# mini-c3.net
KiCad netlist of a schematic drawn in EasyEDA Pro
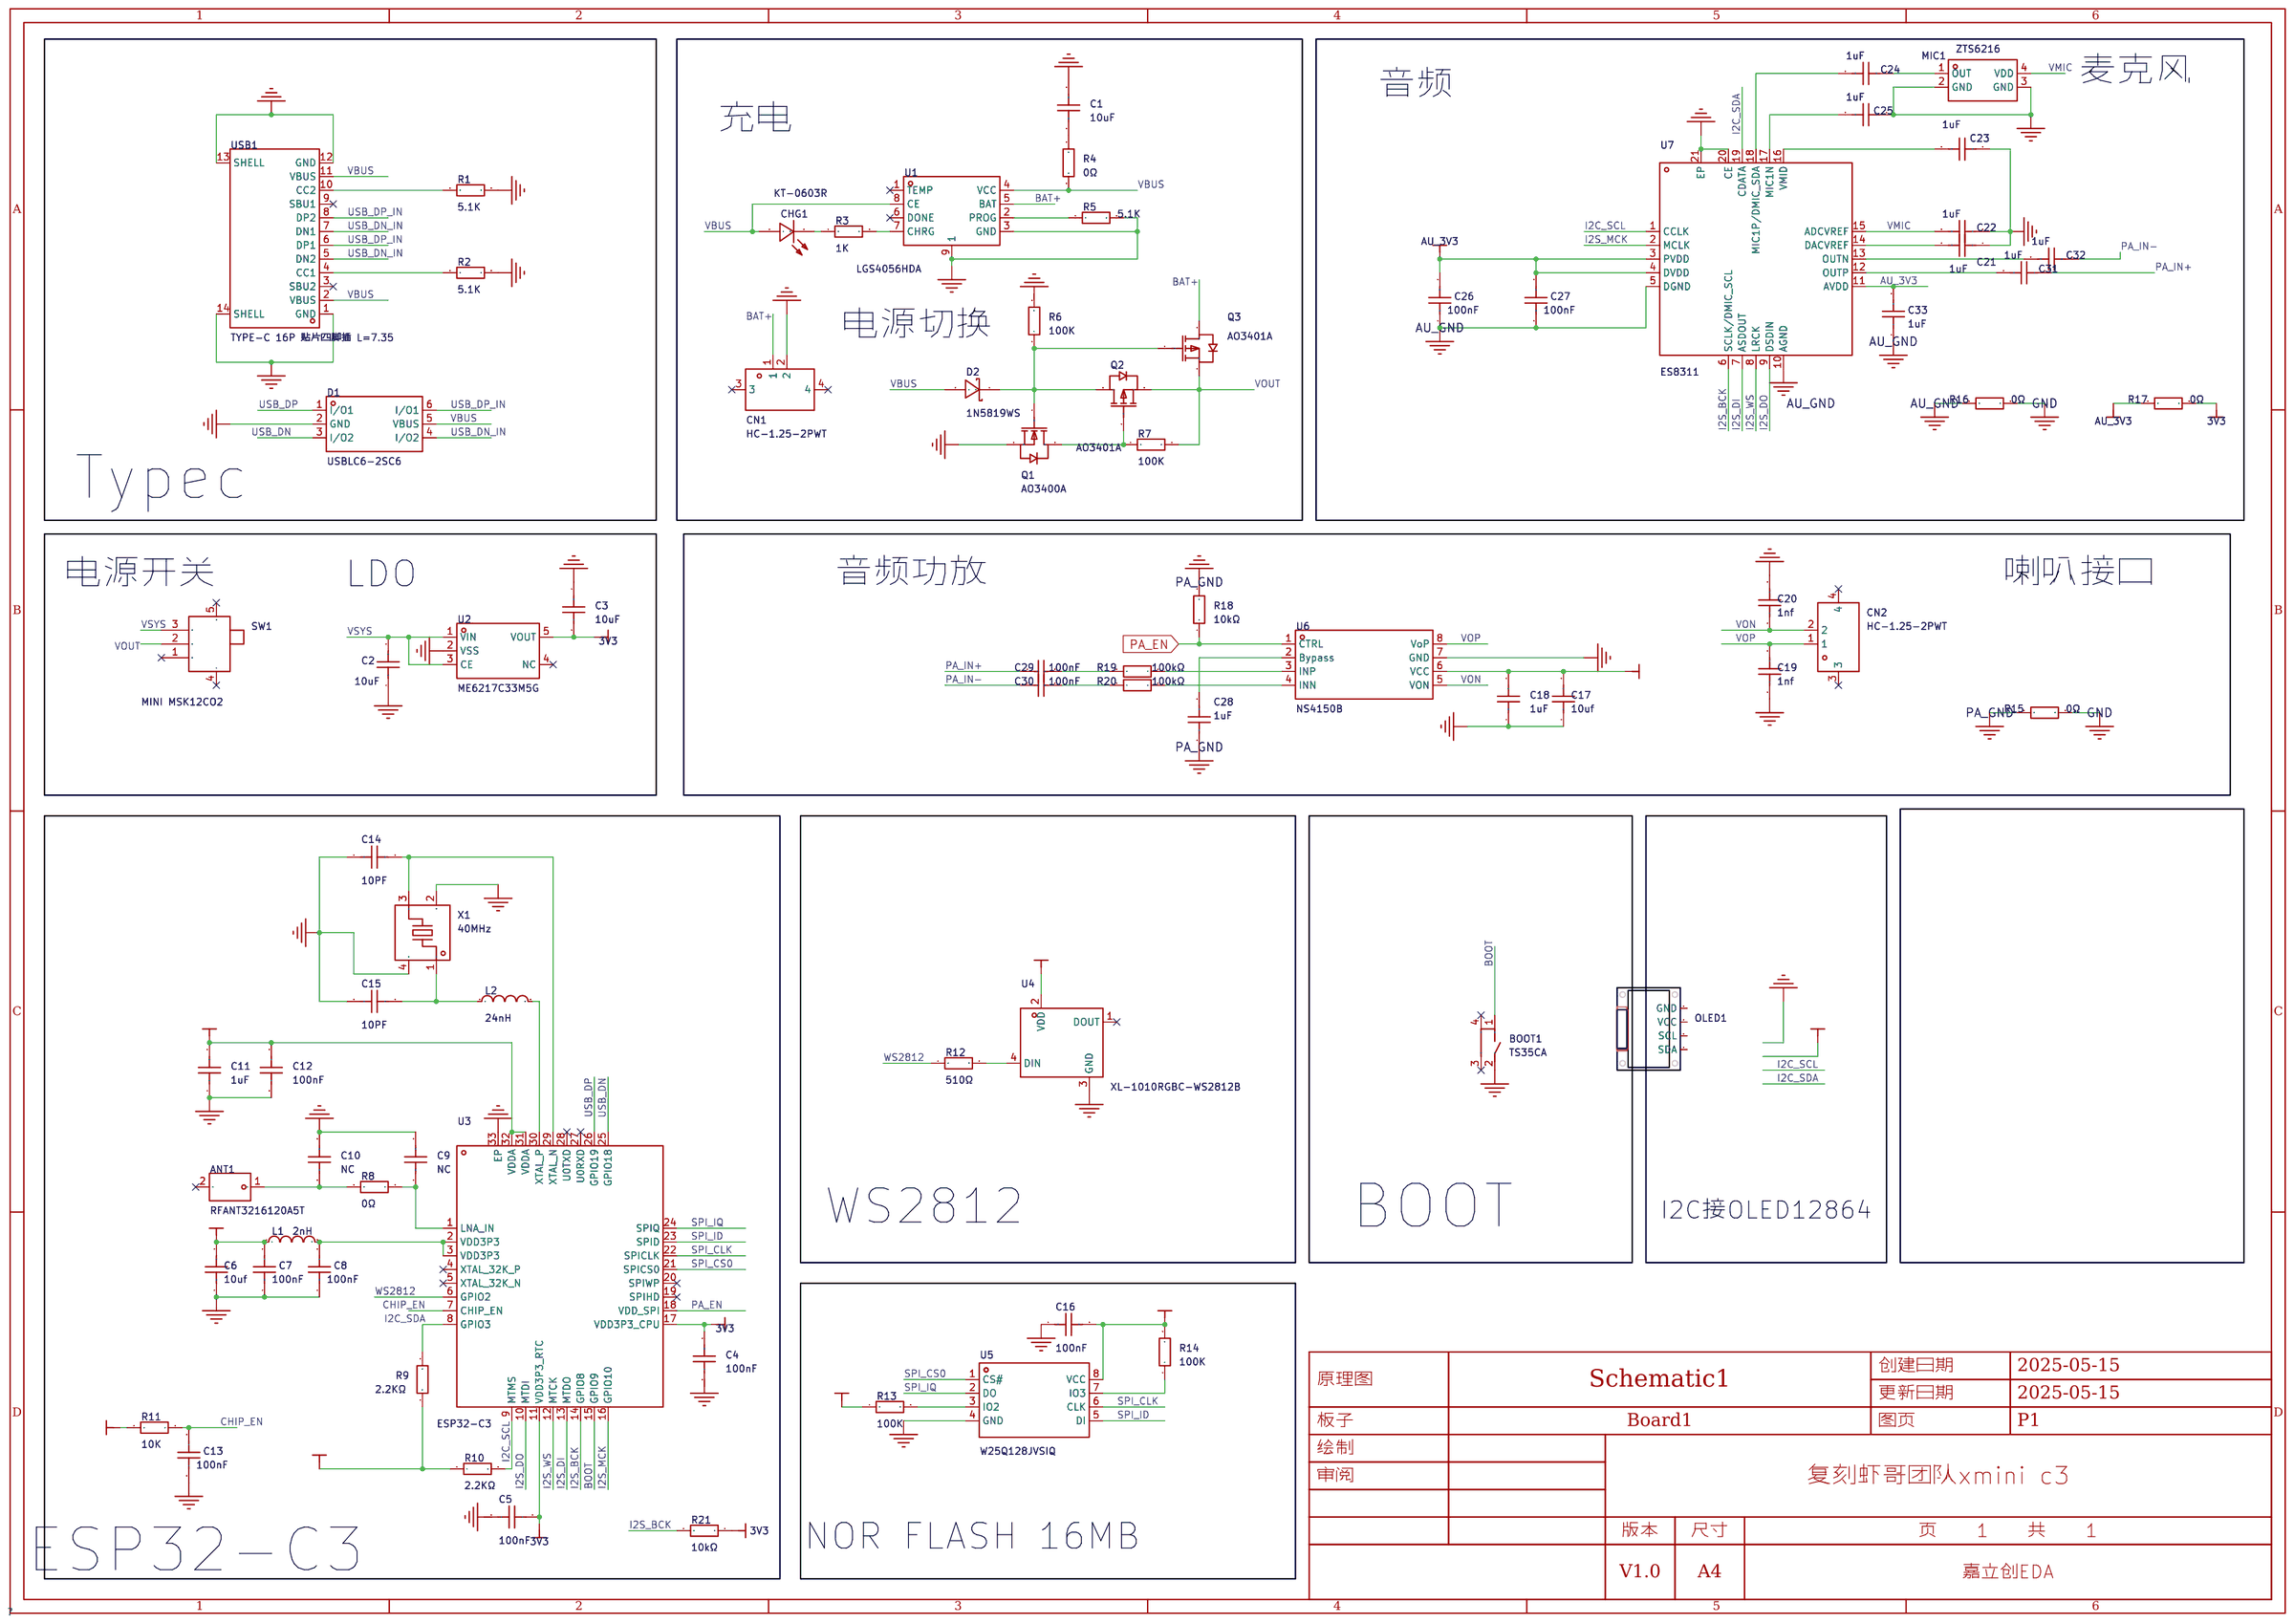
[diagram p0: schematic sheet]

(export (version "E")
  (design (tool "Eeschema 10.0.6"))
  (components
    (comp (ref "ANT1")
      (value "RFANT3216120A5T")
      (footprint "easyedapro:FILTER-SMD_1206-2P-L3.2-W1.6-L")
      (fields (field (name "Manufacturer") "Walsin(华新科)"))
      (libsource (lib "easyedapro") (part "RFANT3216120A5T"))
    )
    (comp (ref "BOOT1")
      (value "TS35CA")
      (footprint "easyedapro:KEY-SMD_TS35CA")
      (fields (field (name "Manufacturer") "SHOU HAN(首韩)"))
      (libsource (lib "easyedapro") (part "TS35CA"))
    )
    (comp (ref "C1")
      (value "10uF")
      (footprint "easyedapro:C0402")
      (libsource (lib "easyedapro") (part "CapAcitance"))
    )
    (comp (ref "C2")
      (value "10uF")
      (footprint "easyedapro:C0402")
      (libsource (lib "easyedapro") (part "CapAcitance"))
    )
    (comp (ref "C3")
      (value "10uF")
      (footprint "easyedapro:C0402")
      (libsource (lib "easyedapro") (part "CapAcitance"))
    )
    (comp (ref "C4")
      (value "100nF")
      (footprint "easyedapro:C0402")
      (libsource (lib "easyedapro") (part "CapAcitance"))
    )
    (comp (ref "C5")
      (value "100nF")
      (footprint "easyedapro:C0402")
      (libsource (lib "easyedapro") (part "CapAcitance"))
    )
    (comp (ref "C6")
      (value "10uf")
      (footprint "easyedapro:C0402")
      (libsource (lib "easyedapro") (part "CapAcitance"))
    )
    (comp (ref "C7")
      (value "100nF")
      (footprint "easyedapro:C0402")
      (libsource (lib "easyedapro") (part "CapAcitance"))
    )
    (comp (ref "C8")
      (value "100nF")
      (footprint "easyedapro:C0402")
      (libsource (lib "easyedapro") (part "CapAcitance"))
    )
    (comp (ref "C9")
      (value "NC")
      (footprint "easyedapro:C0402")
      (libsource (lib "easyedapro") (part "CapAcitance"))
    )
    (comp (ref "C10")
      (value "NC")
      (footprint "easyedapro:C0402")
      (libsource (lib "easyedapro") (part "CapAcitance"))
    )
    (comp (ref "C11")
      (value "1uF")
      (footprint "easyedapro:C0402")
      (libsource (lib "easyedapro") (part "CapAcitance"))
    )
    (comp (ref "C12")
      (value "100nF")
      (footprint "easyedapro:C0402")
      (libsource (lib "easyedapro") (part "CapAcitance"))
    )
    (comp (ref "C13")
      (value "100nF")
      (footprint "easyedapro:C0402")
      (libsource (lib "easyedapro") (part "CapAcitance"))
    )
    (comp (ref "C14")
      (value "10PF")
      (footprint "easyedapro:C0402")
      (libsource (lib "easyedapro") (part "CapAcitance"))
    )
    (comp (ref "C15")
      (value "10PF")
      (footprint "easyedapro:C0402")
      (libsource (lib "easyedapro") (part "CapAcitance"))
    )
    (comp (ref "C16")
      (value "100nF")
      (footprint "easyedapro:C0402")
      (libsource (lib "easyedapro") (part "CapAcitance"))
    )
    (comp (ref "C17")
      (value "10uf")
      (footprint "easyedapro:C0402")
      (libsource (lib "easyedapro") (part "CapAcitance"))
    )
    (comp (ref "C18")
      (value "1uF")
      (footprint "easyedapro:C0402")
      (libsource (lib "easyedapro") (part "CapAcitance"))
    )
    (comp (ref "C19")
      (value "1nf")
      (footprint "easyedapro:C0402")
      (libsource (lib "easyedapro") (part "CapAcitance"))
    )
    (comp (ref "C20")
      (value "1nf")
      (footprint "easyedapro:C0402")
      (libsource (lib "easyedapro") (part "CapAcitance"))
    )
    (comp (ref "C21")
      (value "1uF")
      (footprint "easyedapro:C0402")
      (libsource (lib "easyedapro") (part "CapAcitance"))
    )
    (comp (ref "C22")
      (value "1uF")
      (footprint "easyedapro:C0402")
      (libsource (lib "easyedapro") (part "CapAcitance"))
    )
    (comp (ref "C23")
      (value "1uF")
      (footprint "easyedapro:C0402")
      (libsource (lib "easyedapro") (part "CapAcitance"))
    )
    (comp (ref "C24")
      (value "1uF")
      (footprint "easyedapro:C0402")
      (libsource (lib "easyedapro") (part "CapAcitance"))
    )
    (comp (ref "C25")
      (value "1uF")
      (footprint "easyedapro:C0402")
      (libsource (lib "easyedapro") (part "CapAcitance"))
    )
    (comp (ref "C26")
      (value "100nF")
      (footprint "easyedapro:C0402")
      (libsource (lib "easyedapro") (part "CapAcitance"))
    )
    (comp (ref "C27")
      (value "100nF")
      (footprint "easyedapro:C0402")
      (libsource (lib "easyedapro") (part "CapAcitance"))
    )
    (comp (ref "C28")
      (value "1uF")
      (footprint "easyedapro:C0402")
      (fields
        (field (name "Manufacturer Part") "CL05A105KA5NQNC")
        (field (name "Manufacturer") "SAMSUNG(三星)")
      )
      (libsource (lib "easyedapro") (part "CL05A105KA5NQNC"))
    )
    (comp (ref "C29")
      (value "100nF")
      (footprint "easyedapro:C0402")
      (fields
        (field (name "Manufacturer Part") "CL05B104KO5NNNC")
        (field (name "Manufacturer") "SAMSUNG(三星)")
      )
      (libsource (lib "easyedapro") (part "CL05B104KO5NNNC"))
    )
    (comp (ref "C30")
      (value "100nF")
      (footprint "easyedapro:C0402")
      (fields
        (field (name "Manufacturer Part") "CL05B104KO5NNNC")
        (field (name "Manufacturer") "SAMSUNG(三星)")
      )
      (libsource (lib "easyedapro") (part "CL05B104KO5NNNC"))
    )
    (comp (ref "C31")
      (value "1uF")
      (footprint "easyedapro:C0402")
      (libsource (lib "easyedapro") (part "CapAcitance"))
    )
    (comp (ref "C32")
      (value "1uF")
      (footprint "easyedapro:C0402")
      (libsource (lib "easyedapro") (part "CapAcitance"))
    )
    (comp (ref "C33")
      (value "1uF")
      (footprint "easyedapro:C0402")
      (fields
        (field (name "Manufacturer Part") "CL05A105KA5NQNC")
        (field (name "Manufacturer") "SAMSUNG(三星)")
      )
      (libsource (lib "easyedapro") (part "CL05A105KA5NQNC"))
    )
    (comp (ref "CHG1")
      (value "KT-0603R")
      (footprint "easyedapro:LED0603-RD")
      (fields (field (name "Manufacturer") "KENTO"))
      (libsource (lib "easyedapro") (part "KT-0603R"))
    )
    (comp (ref "CN1")
      (value "HC-1.25-2PWT")
      (footprint "easyedapro:CONN-SMD_2P-P1.25-HC-1.25-2PWT")
      (fields (field (name "Manufacturer") "HCTL(华灿天禄)"))
      (libsource (lib "easyedapro") (part "HC-1.25-2PWT"))
    )
    (comp (ref "CN2")
      (value "HC-1.25-2PWT")
      (footprint "easyedapro:CONN-SMD_2P-P1.25-HC-1.25-2PWT")
      (fields (field (name "Manufacturer") "HCTL(华灿天禄)"))
      (libsource (lib "easyedapro") (part "HC-1.25-2PWT"))
    )
    (comp (ref "D1")
      (value "USBLC6-2SC6")
      (footprint "easyedapro:SOT-23-6_L2.9-W1.6-P0.95-LS2.8-BL")
      (fields (field (name "Manufacturer") "UMW(友台半导体)"))
      (libsource (lib "easyedapro") (part "USBLC6-2SC6_C2687116"))
    )
    (comp (ref "D2")
      (value "1N5819WS")
      (footprint "easyedapro:SOD-323_L1.8-W1.3-LS2.5-RD")
      (fields (field (name "Manufacturer") "Hottech(合科泰)"))
      (libsource (lib "easyedapro") (part "1N5819WS"))
    )
    (comp (ref "L1")
      (value "2nH")
      (footprint "easyedapro:L0402")
      (libsource (lib "easyedapro") (part "SDCL1005C10NJTDFM01"))
    )
    (comp (ref "L2")
      (value "24nH")
      (footprint "easyedapro:L0402")
      (libsource (lib "easyedapro") (part "SDCL1005C10NJTDFM01"))
    )
    (comp (ref "MIC1")
      (value "ZTS6216")
      (footprint "easyedapro:MIC-SMD_4P-L2.8-W1.9-P1.84-TL")
      (description "方向:全指向;信噪比:65dB;灵敏度:-38dB;阻抗:100Ω;")
      (fields (field (name "Manufacturer") "ZILLTEK(钰太)"))
      (libsource (lib "easyedapro") (part "ZTS6216"))
    )
    (comp (ref "OLED1")
      (value "~")
      (footprint "easyedapro:0.96OLED_4P")
      (libsource (lib "easyedapro") (part "0.96OLED模块_4P"))
    )
    (comp (ref "Q1")
      (value "AO3400A")
      (footprint "easyedapro:SOT-23-3_L2.9-W1.3-P1.90-LS2.4-BR")
      (fields (field (name "Manufacturer") "AOS"))
      (libsource (lib "easyedapro") (part "AO3400A"))
    )
    (comp (ref "Q2")
      (value "AO3401A")
      (footprint "easyedapro:SOT-23_L2.9-W1.3-P1.90-LS2.4-BR")
      (fields (field (name "Manufacturer") "AOS"))
      (libsource (lib "easyedapro") (part "AO3401A"))
    )
    (comp (ref "Q3")
      (value "AO3401A")
      (footprint "easyedapro:SOT-23_L2.9-W1.3-P1.90-LS2.4-BR")
      (fields (field (name "Manufacturer") "AOS"))
      (libsource (lib "easyedapro") (part "AO3401A"))
    )
    (comp (ref "R1") (value "5.1K") (footprint "easyedapro:R0402") (libsource (lib "easyedapro") (part "电阻")))
    (comp (ref "R2") (value "5.1K") (footprint "easyedapro:R0402") (libsource (lib "easyedapro") (part "电阻")))
    (comp (ref "R3") (value "1K") (footprint "easyedapro:R0402") (libsource (lib "easyedapro") (part "电阻")))
    (comp (ref "R4") (value "0Ω") (footprint "easyedapro:R0402") (libsource (lib "easyedapro") (part "电阻")))
    (comp (ref "R5") (value "5.1K") (footprint "easyedapro:R0402") (libsource (lib "easyedapro") (part "电阻")))
    (comp (ref "R6") (value "100K") (footprint "easyedapro:R0402") (libsource (lib "easyedapro") (part "电阻")))
    (comp (ref "R7") (value "100K") (footprint "easyedapro:R0402") (libsource (lib "easyedapro") (part "电阻")))
    (comp (ref "R8") (value "0Ω") (footprint "easyedapro:R0402") (libsource (lib "easyedapro") (part "电阻")))
    (comp (ref "R9")
      (value "2.2KΩ")
      (footprint "easyedapro:R0402")
      (libsource (lib "easyedapro") (part "电阻"))
    )
    (comp (ref "R10")
      (value "2.2KΩ")
      (footprint "easyedapro:R0402")
      (libsource (lib "easyedapro") (part "电阻"))
    )
    (comp (ref "R11") (value "10K") (footprint "easyedapro:R0402") (libsource (lib "easyedapro") (part "电阻")))
    (comp (ref "R12")
      (value "510Ω")
      (footprint "easyedapro:R0402")
      (libsource (lib "easyedapro") (part "电阻"))
    )
    (comp (ref "R13")
      (value "100K")
      (footprint "easyedapro:R0402")
      (libsource (lib "easyedapro") (part "电阻"))
    )
    (comp (ref "R14")
      (value "100K")
      (footprint "easyedapro:R0402")
      (libsource (lib "easyedapro") (part "电阻"))
    )
    (comp (ref "R15")
      (value "0Ω")
      (footprint "easyedapro:R0402")
      (fields
        (field (name "Manufacturer Part") "0402WGF0000TCE")
        (field (name "Manufacturer") "UNI-ROYAL(厚声)")
      )
      (libsource (lib "easyedapro") (part "0402WGF0000TCE"))
    )
    (comp (ref "R16")
      (value "0Ω")
      (footprint "easyedapro:R0402")
      (fields
        (field (name "Manufacturer Part") "0402WGF0000TCE")
        (field (name "Manufacturer") "UNI-ROYAL(厚声)")
      )
      (libsource (lib "easyedapro") (part "0402WGF0000TCE"))
    )
    (comp (ref "R17")
      (value "0Ω")
      (footprint "easyedapro:R0402")
      (fields
        (field (name "Manufacturer Part") "0402WGF0000TCE")
        (field (name "Manufacturer") "UNI-ROYAL(厚声)")
      )
      (libsource (lib "easyedapro") (part "0402WGF0000TCE"))
    )
    (comp (ref "R18")
      (value "10kΩ")
      (footprint "easyedapro:R0402")
      (fields
        (field (name "Manufacturer Part") "0402WGF1002TCE")
        (field (name "Manufacturer") "UNI-ROYAL(厚声)")
      )
      (libsource (lib "easyedapro") (part "0402WGF1002TCE"))
    )
    (comp (ref "R19")
      (value "100kΩ")
      (footprint "easyedapro:R0402")
      (fields
        (field (name "Manufacturer Part") "0402WGF1003TCE")
        (field (name "Manufacturer") "UNI-ROYAL(厚声)")
      )
      (libsource (lib "easyedapro") (part "0402WGF1003TCE"))
    )
    (comp (ref "R20")
      (value "100kΩ")
      (footprint "easyedapro:R0402")
      (fields
        (field (name "Manufacturer Part") "0402WGF1003TCE")
        (field (name "Manufacturer") "UNI-ROYAL(厚声)")
      )
      (libsource (lib "easyedapro") (part "0402WGF1003TCE"))
    )
    (comp (ref "R21")
      (value "10kΩ")
      (footprint "easyedapro:R0402")
      (fields
        (field (name "Manufacturer Part") "0402WGF1002TCE")
        (field (name "Manufacturer") "UNI-ROYAL(厚声)")
      )
      (libsource (lib "easyedapro") (part "0402WGF1002TCE"))
    )
    (comp (ref "SW1")
      (value "MINI MSK12CO2")
      (footprint "easyedapro:SW-SMD_MSK12CO2")
      (fields (field (name "Manufacturer") "SHOU HAN(首韩)"))
      (libsource (lib "easyedapro") (part "MINI MSK12CO2"))
    )
    (comp (ref "U1")
      (value "LGS4056HDA")
      (footprint "easyedapro:DFN-8_L2.0-W2.0-P0.50-TL-EP1.6")
      (fields (field (name "Manufacturer") "Legend-Si(棱晶半导体)"))
      (libsource (lib "easyedapro") (part "LGS4056H"))
    )
    (comp (ref "U2")
      (value "ME6217C33M5G")
      (footprint "easyedapro:SOT-23-5_L3.0-W1.7-P0.95-LS2.8-BR")
      (fields (field (name "Manufacturer") "MICRONE(南京微盟)"))
      (libsource (lib "easyedapro") (part "ME6217C33M5G"))
    )
    (comp (ref "U3")
      (value "ESP32-C3")
      (footprint "easyedapro:QFN-32_L5.0-W5.0-P0.50-TL-EP3.7")
      (fields (field (name "Manufacturer") "ESPRESSIF(乐鑫)"))
      (libsource (lib "easyedapro") (part "ESP32-C3"))
    )
    (comp (ref "U4")
      (value "XL-1010RGBC-WS2812B")
      (footprint "easyedapro:LED-SMD_4P-L1.0-W1.0-TL_XL-1010RGBC-WS2812B")
      (fields (field (name "Manufacturer") "XINGLIGHT(成兴光)"))
      (libsource (lib "easyedapro") (part "XL-1010RGBC-WS2812B"))
    )
    (comp (ref "U5")
      (value "W25Q128JVSIQ")
      (footprint "easyedapro:SOIC-8_L5.3-W5.3-P1.27-LS8.0-BL")
      (fields (field (name "Manufacturer") "WINBOND(华邦)"))
      (libsource (lib "easyedapro") (part "W25Q128JVSIQTR"))
    )
    (comp (ref "U6")
      (value "NS4150B")
      (footprint "easyedapro:MSOP-8_L3.0-W3.0-P0.65-LS5.0-BL")
      (fields (field (name "Manufacturer") "Nsiway(纳芯威)"))
      (libsource (lib "easyedapro") (part "NS4150"))
    )
    (comp (ref "U7")
      (value "ES8311")
      (footprint "easyedapro:WQFN-20_L3.0-W3.0-P0.40-BL-EP1.7")
      (fields (field (name "Manufacturer") "Everest-semi(顺芯)"))
      (libsource (lib "easyedapro") (part "ES8311"))
    )
    (comp (ref "USB1")
      (value "TYPE-C 16P 贴片四脚插 L=7.35")
      (footprint "easyedapro:USB-C-SMD_TYPE-C-6PIN-2MD-073")
      (libsource (lib "easyedapro") (part "TYPE-C 16P 贴片四脚插 L=7.35"))
    )
    (comp (ref "X1")
      (value "40MHz")
      (footprint "easyedapro:CRYSTAL-SMD_4P-L2.5-W2.0-BL")
      (fields (field (name "Manufacturer Part") "X252040MMB4SI") (field (name "Manufacturer") "YXC(扬兴晶振)"))
      (libsource (lib "easyedapro") (part "X252040MMB4SI"))
    )
  )
  (nets
    (net (code "1") (name "/BAT+") (class "Default")
      (node (ref "CN1") (pin "1") (pinfunction "1_1") (pintype "unspecified"))
      (node (ref "Q3") (pin "3") (pinfunction "D_3") (pintype "unspecified"))
      (node (ref "U1") (pin "5") (pinfunction "BAT_5") (pintype "unspecified"))
    )
    (net (code "2") (name "/BOOT") (class "Default")
      (node (ref "BOOT1") (pin "1") (pinfunction "1_1") (pintype "unspecified"))
      (node (ref "U3") (pin "15") (pinfunction "GPIO9_15") (pintype "unspecified"))
    )
    (net (code "3") (name "/CHIP_EN") (class "Default")
      (node (ref "C13") (pin "2") (pinfunction "2_2") (pintype "input"))
      (node (ref "R11") (pin "2") (pinfunction "2_2") (pintype "input"))
      (node (ref "U3") (pin "7") (pinfunction "CHIP_EN_7") (pintype "unspecified"))
    )
    (net (code "4") (name "/I2C_SCL") (class "Default")
      (node (ref "R10") (pin "2") (pinfunction "2_2") (pintype "input"))
      (node (ref "U3") (pin "9") (pinfunction "MTMS_9") (pintype "unspecified"))
      (node (ref "U7") (pin "1") (pinfunction "CCLK_1") (pintype "input"))
    )
    (net (code "5") (name "/I2C_SDA") (class "Default")
      (node (ref "R9") (pin "2") (pinfunction "2_2") (pintype "input"))
      (node (ref "U3") (pin "8") (pinfunction "GPIO3_8") (pintype "unspecified"))
      (node (ref "U7") (pin "19") (pinfunction "CDATA_19") (pintype "input"))
    )
    (net (code "6") (name "/I2S_BCK") (class "Default")
      (node (ref "R21") (pin "2") (pinfunction "2_2") (pintype "input"))
      (node (ref "U3") (pin "14") (pinfunction "GPIO8_14") (pintype "unspecified"))
      (node (ref "U7") (pin "6") (pinfunction "SCLK/DMIC_SCL_6") (pintype "input"))
    )
    (net (code "7") (name "/I2S_DI") (class "Default")
      (node (ref "U3") (pin "13") (pinfunction "MTDO_13") (pintype "unspecified"))
      (node (ref "U7") (pin "7") (pinfunction "ASDOUT_7") (pintype "input"))
    )
    (net (code "8") (name "/I2S_DO") (class "Default")
      (node (ref "U3") (pin "10") (pinfunction "MTDI_10") (pintype "unspecified"))
      (node (ref "U7") (pin "9") (pinfunction "DSDIN_9") (pintype "input"))
    )
    (net (code "9") (name "/I2S_MCK") (class "Default")
      (node (ref "U3") (pin "16") (pinfunction "GPIO10_16") (pintype "unspecified"))
      (node (ref "U7") (pin "2") (pinfunction "MCLK_2") (pintype "input"))
    )
    (net (code "10") (name "/I2S_WS") (class "Default")
      (node (ref "U3") (pin "12") (pinfunction "MTCK_12") (pintype "unspecified"))
      (node (ref "U7") (pin "8") (pinfunction "LRCK_8") (pintype "input"))
    )
    (net (code "11") (name "/PA_IN+") (class "Default")
      (node (ref "C29") (pin "1") (pinfunction "1_1") (pintype "input"))
      (node (ref "C31") (pin "1") (pinfunction "1_1") (pintype "input"))
    )
    (net (code "12") (name "/PA_IN-") (class "Default")
      (node (ref "C30") (pin "1") (pinfunction "1_1") (pintype "input"))
      (node (ref "C32") (pin "1") (pinfunction "1_1") (pintype "input"))
    )
    (net (code "13") (name "/SPI_CLK") (class "Default")
      (node (ref "U3") (pin "22") (pinfunction "SPICLK_22") (pintype "unspecified"))
      (node (ref "U5") (pin "6") (pinfunction "CLK_6") (pintype "unspecified"))
    )
    (net (code "14") (name "/SPI_CS0") (class "Default")
      (node (ref "U3") (pin "21") (pinfunction "SPICS0_21") (pintype "unspecified"))
      (node (ref "U5") (pin "1") (pinfunction "CS#_1") (pintype "unspecified"))
    )
    (net (code "15") (name "/SPI_ID") (class "Default")
      (node (ref "U3") (pin "23") (pinfunction "SPID_23") (pintype "unspecified"))
      (node (ref "U5") (pin "5") (pinfunction "DI_5") (pintype "unspecified"))
    )
    (net (code "16") (name "/SPI_IQ") (class "Default")
      (node (ref "U3") (pin "24") (pinfunction "SPIQ_24") (pintype "unspecified"))
      (node (ref "U5") (pin "2") (pinfunction "DO_2") (pintype "unspecified"))
    )
    (net (code "17") (name "/USB_DN") (class "Default")
      (node (ref "D1") (pin "3") (pinfunction "I/O2_3") (pintype "unspecified"))
      (node (ref "U3") (pin "25") (pinfunction "GPIO18_25") (pintype "unspecified"))
    )
    (net (code "18") (name "/USB_DN_IN") (class "Default")
      (node (ref "D1") (pin "4") (pinfunction "I/O2_4") (pintype "unspecified"))
      (node (ref "USB1") (pin "5") (pinfunction "DN2_5") (pintype "unspecified"))
      (node (ref "USB1") (pin "7") (pinfunction "DN1_7") (pintype "unspecified"))
    )
    (net (code "19") (name "/USB_DP") (class "Default")
      (node (ref "D1") (pin "1") (pinfunction "I/O1_1") (pintype "unspecified"))
      (node (ref "U3") (pin "26") (pinfunction "GPIO19_26") (pintype "unspecified"))
    )
    (net (code "20") (name "/USB_DP_IN") (class "Default")
      (node (ref "D1") (pin "6") (pinfunction "I/O1_6") (pintype "unspecified"))
      (node (ref "USB1") (pin "6") (pinfunction "DP1_6") (pintype "unspecified"))
      (node (ref "USB1") (pin "8") (pinfunction "DP2_8") (pintype "unspecified"))
    )
    (net (code "21") (name "/VBUS") (class "Default")
      (node (ref "CHG1") (pin "2") (pinfunction "A_2") (pintype "unspecified"))
      (node (ref "D1") (pin "5") (pinfunction "VBUS_5") (pintype "unspecified"))
      (node (ref "D2") (pin "2") (pinfunction "A_2") (pintype "unspecified"))
      (node (ref "R4") (pin "1") (pinfunction "1_1") (pintype "input"))
      (node (ref "U1") (pin "4") (pinfunction "VCC_4") (pintype "unspecified"))
      (node (ref "U1") (pin "8") (pinfunction "CE_8") (pintype "unspecified"))
      (node (ref "USB1") (pin "11") (pinfunction "VBUS_11") (pintype "unspecified"))
      (node (ref "USB1") (pin "2") (pinfunction "VBUS_2") (pintype "unspecified"))
    )
    (net (code "22") (name "/VMIC") (class "Default")
      (node (ref "C22") (pin "2") (pinfunction "2_2") (pintype "input"))
      (node (ref "MIC1") (pin "4") (pinfunction "VDD_4") (pintype "input"))
      (node (ref "U7") (pin "15") (pinfunction "ADCVREF_15") (pintype "input"))
    )
    (net (code "23") (name "/VON") (class "Default")
      (node (ref "C20") (pin "1") (pinfunction "1_1") (pintype "input"))
      (node (ref "CN2") (pin "2") (pinfunction "2_2") (pintype "unspecified"))
      (node (ref "U6") (pin "5") (pinfunction "VON_5") (pintype "unspecified"))
    )
    (net (code "24") (name "/VOP") (class "Default")
      (node (ref "C19") (pin "2") (pinfunction "2_2") (pintype "input"))
      (node (ref "CN2") (pin "1") (pinfunction "1_1") (pintype "unspecified"))
      (node (ref "U6") (pin "8") (pinfunction "VoP_8") (pintype "unspecified"))
    )
    (net (code "25") (name "/VOUT") (class "Default")
      (node (ref "Q2") (pin "2") (pinfunction "S_2") (pintype "unspecified"))
      (node (ref "Q3") (pin "2") (pinfunction "S_2") (pintype "unspecified"))
      (node (ref "R7") (pin "2") (pinfunction "2_2") (pintype "input"))
      (node (ref "SW1") (pin "2") (pinfunction "2_2") (pintype "unspecified"))
    )
    (net (code "26") (name "/WS2812") (class "Default")
      (node (ref "R12") (pin "1") (pinfunction "1_1") (pintype "input"))
      (node (ref "U3") (pin "6") (pinfunction "GPIO2_6") (pintype "unspecified"))
    )
    (net (code "27") (name "3V3") (class "Default")
      (node (ref "C11") (pin "2") (pinfunction "2_2") (pintype "input"))
      (node (ref "C12") (pin "1") (pinfunction "1_1") (pintype "input"))
      (node (ref "C16") (pin "2") (pinfunction "2_2") (pintype "input"))
      (node (ref "C3") (pin "2") (pinfunction "2_2") (pintype "input"))
      (node (ref "C4") (pin "1") (pinfunction "1_1") (pintype "input"))
      (node (ref "C5") (pin "1") (pinfunction "1_1") (pintype "input"))
      (node (ref "C6") (pin "2") (pinfunction "2_2") (pintype "input"))
      (node (ref "C7") (pin "2") (pinfunction "2_2") (pintype "input"))
      (node (ref "L1") (pin "1") (pinfunction "1_1") (pintype "unspecified"))
      (node (ref "R10") (pin "1") (pinfunction "1_1") (pintype "input"))
      (node (ref "R11") (pin "1") (pinfunction "1_1") (pintype "input"))
      (node (ref "R13") (pin "1") (pinfunction "1_1") (pintype "input"))
      (node (ref "R14") (pin "2") (pinfunction "2_2") (pintype "input"))
      (node (ref "R17") (pin "2") (pinfunction "2_2") (pintype "input"))
      (node (ref "R21") (pin "1") (pinfunction "1_1") (pintype "input"))
      (node (ref "R9") (pin "1") (pinfunction "1_1") (pintype "input"))
      (node (ref "U2") (pin "5") (pinfunction "VOUT_5") (pintype "unspecified"))
      (node (ref "U3") (pin "11") (pinfunction "VDD3P3_RTC_11") (pintype "unspecified"))
      (node (ref "U3") (pin "17") (pinfunction "VDD3P3_CPU_17") (pintype "unspecified"))
      (node (ref "U3") (pin "31") (pinfunction "VDDA_31") (pintype "unspecified"))
      (node (ref "U3") (pin "32") (pinfunction "VDDA_32") (pintype "unspecified"))
      (node (ref "U5") (pin "8") (pinfunction "VCC_8") (pintype "unspecified"))
    )
    (net (code "28") (name "AU_3V3") (class "Default")
      (node (ref "C26") (pin "2") (pinfunction "2_2") (pintype "input"))
      (node (ref "C27") (pin "2") (pinfunction "2_2") (pintype "input"))
      (node (ref "C33") (pin "2") (pinfunction "2_2") (pintype "input"))
      (node (ref "R17") (pin "1") (pinfunction "1_1") (pintype "input"))
      (node (ref "U7") (pin "11") (pinfunction "AVDD_11") (pintype "input"))
      (node (ref "U7") (pin "3") (pinfunction "PVDD_3") (pintype "input"))
      (node (ref "U7") (pin "4") (pinfunction "DVDD_4") (pintype "input"))
    )
    (net (code "29") (name "AU_GND") (class "Default")
      (node (ref "C21") (pin "1") (pinfunction "1_1") (pintype "input"))
      (node (ref "C22") (pin "1") (pinfunction "1_1") (pintype "input"))
      (node (ref "C23") (pin "1") (pinfunction "1_1") (pintype "input"))
      (node (ref "C25") (pin "1") (pinfunction "1_1") (pintype "input"))
      (node (ref "C26") (pin "1") (pinfunction "1_1") (pintype "input"))
      (node (ref "C27") (pin "1") (pinfunction "1_1") (pintype "input"))
      (node (ref "C33") (pin "1") (pinfunction "1_1") (pintype "input"))
      (node (ref "MIC1") (pin "2") (pinfunction "GND_2") (pintype "input"))
      (node (ref "MIC1") (pin "3") (pinfunction "GND_3") (pintype "input"))
      (node (ref "R16") (pin "1") (pinfunction "1_1") (pintype "input"))
      (node (ref "U7") (pin "10") (pinfunction "AGND_10") (pintype "input"))
      (node (ref "U7") (pin "20") (pinfunction "CE_20") (pintype "input"))
      (node (ref "U7") (pin "21") (pinfunction "EP_21") (pintype "input"))
      (node (ref "U7") (pin "5") (pinfunction "DGND_5") (pintype "input"))
    )
    (net (code "30") (name "GND") (class "Default")
      (node (ref "BOOT1") (pin "2") (pinfunction "2_2") (pintype "unspecified"))
      (node (ref "C1") (pin "2") (pinfunction "2_2") (pintype "input"))
      (node (ref "C10") (pin "2") (pinfunction "2_2") (pintype "input"))
      (node (ref "C11") (pin "1") (pinfunction "1_1") (pintype "input"))
      (node (ref "C12") (pin "2") (pinfunction "2_2") (pintype "input"))
      (node (ref "C13") (pin "1") (pinfunction "1_1") (pintype "input"))
      (node (ref "C14") (pin "1") (pinfunction "1_1") (pintype "input"))
      (node (ref "C15") (pin "1") (pinfunction "1_1") (pintype "input"))
      (node (ref "C16") (pin "1") (pinfunction "1_1") (pintype "input"))
      (node (ref "C2") (pin "1") (pinfunction "1_1") (pintype "input"))
      (node (ref "C3") (pin "1") (pinfunction "1_1") (pintype "input"))
      (node (ref "C4") (pin "2") (pinfunction "2_2") (pintype "input"))
      (node (ref "C5") (pin "2") (pinfunction "2_2") (pintype "input"))
      (node (ref "C6") (pin "1") (pinfunction "1_1") (pintype "input"))
      (node (ref "C7") (pin "1") (pinfunction "1_1") (pintype "input"))
      (node (ref "C8") (pin "1") (pinfunction "1_1") (pintype "input"))
      (node (ref "C9") (pin "2") (pinfunction "2_2") (pintype "input"))
      (node (ref "CN1") (pin "2") (pinfunction "2_2") (pintype "unspecified"))
      (node (ref "D1") (pin "2") (pinfunction "GND_2") (pintype "unspecified"))
      (node (ref "Q1") (pin "2") (pinfunction "S_2") (pintype "unspecified"))
      (node (ref "R1") (pin "2") (pinfunction "2_2") (pintype "input"))
      (node (ref "R15") (pin "2") (pinfunction "2_2") (pintype "input"))
      (node (ref "R16") (pin "2") (pinfunction "2_2") (pintype "input"))
      (node (ref "R2") (pin "2") (pinfunction "2_2") (pintype "input"))
      (node (ref "R5") (pin "2") (pinfunction "2_2") (pintype "input"))
      (node (ref "R6") (pin "2") (pinfunction "2_2") (pintype "input"))
      (node (ref "U1") (pin "3") (pinfunction "GND_3") (pintype "unspecified"))
      (node (ref "U1") (pin "9") (pinfunction "1_9") (pintype "unspecified"))
      (node (ref "U2") (pin "2") (pinfunction "VSS_2") (pintype "unspecified"))
      (node (ref "U3") (pin "33") (pinfunction "EP_33") (pintype "unspecified"))
      (node (ref "U4") (pin "3") (pinfunction "GND_3") (pintype "unspecified"))
      (node (ref "U5") (pin "4") (pinfunction "GND_4") (pintype "unspecified"))
      (node (ref "USB1") (pin "1") (pinfunction "GND_1") (pintype "unspecified"))
      (node (ref "USB1") (pin "12") (pinfunction "GND_12") (pintype "unspecified"))
      (node (ref "USB1") (pin "13") (pinfunction "SHELL_13") (pintype "unspecified"))
      (node (ref "USB1") (pin "14") (pinfunction "SHELL_14") (pintype "unspecified"))
      (node (ref "X1") (pin "2") (pinfunction "GND_2") (pintype "input"))
      (node (ref "X1") (pin "4") (pinfunction "GND_4") (pintype "input"))
    )
    (net (code "31") (name "Net-(ANT1-Pad1)") (class "Default")
      (node (ref "ANT1") (pin "1") (pinfunction "1_1") (pintype "unspecified"))
      (node (ref "C10") (pin "1") (pinfunction "1_1") (pintype "input"))
      (node (ref "R8") (pin "1") (pinfunction "1_1") (pintype "input"))
    )
    (net (code "32") (name "Net-(C1-Pad1)") (class "Default")
      (node (ref "C1") (pin "1") (pinfunction "1_1") (pintype "input"))
      (node (ref "R4") (pin "2") (pinfunction "2_2") (pintype "input"))
    )
    (net (code "33") (name "Net-(C8-Pad2)") (class "Default")
      (node (ref "C8") (pin "2") (pinfunction "2_2") (pintype "input"))
      (node (ref "L1") (pin "2") (pinfunction "2_2") (pintype "unspecified"))
      (node (ref "U3") (pin "2") (pinfunction "VDD3P3_2") (pintype "unspecified"))
      (node (ref "U3") (pin "3") (pinfunction "VDD3P3_3") (pintype "unspecified"))
    )
    (net (code "34") (name "Net-(C15-Pad2)") (class "Default")
      (node (ref "C15") (pin "2") (pinfunction "2_2") (pintype "input"))
      (node (ref "L2") (pin "1") (pinfunction "1_1") (pintype "unspecified"))
      (node (ref "X1") (pin "1") (pinfunction "1_1") (pintype "input"))
    )
    (net (code "35") (name "Net-(C29-Pad2)") (class "Default")
      (node (ref "C29") (pin "2") (pinfunction "2_2") (pintype "input"))
      (node (ref "R19") (pin "2") (pinfunction "2_2") (pintype "input"))
    )
    (net (code "36") (name "Net-(C30-Pad2)") (class "Default")
      (node (ref "C30") (pin "2") (pinfunction "2_2") (pintype "input"))
      (node (ref "R20") (pin "2") (pinfunction "2_2") (pintype "input"))
    )
    (net (code "37") (name "Net-(CHG1-K)") (class "Default")
      (node (ref "CHG1") (pin "1") (pinfunction "K_1") (pintype "unspecified"))
      (node (ref "R3") (pin "1") (pinfunction "1_1") (pintype "input"))
    )
    (net (code "38") (name "Net-(D2-K)") (class "Default")
      (node (ref "D2") (pin "1") (pinfunction "K_1") (pintype "unspecified"))
      (node (ref "Q1") (pin "1") (pinfunction "G_1") (pintype "unspecified"))
      (node (ref "Q2") (pin "3") (pinfunction "D_3") (pintype "unspecified"))
      (node (ref "Q3") (pin "1") (pinfunction "G_1") (pintype "unspecified"))
      (node (ref "R6") (pin "1") (pinfunction "1_1") (pintype "input"))
    )
    (net (code "39") (name "Net-(MIC1-OUT)") (class "Default")
      (node (ref "C24") (pin "1") (pinfunction "1_1") (pintype "input"))
      (node (ref "MIC1") (pin "1") (pinfunction "OUT_1") (pintype "input"))
    )
    (net (code "40") (name "Net-(Q1-D)") (class "Default")
      (node (ref "Q1") (pin "3") (pinfunction "D_3") (pintype "unspecified"))
      (node (ref "Q2") (pin "1") (pinfunction "G_1") (pintype "unspecified"))
      (node (ref "R7") (pin "1") (pinfunction "1_1") (pintype "input"))
    )
    (net (code "41") (name "Net-(U1-CHRG)") (class "Default")
      (node (ref "R3") (pin "2") (pinfunction "2_2") (pintype "input"))
      (node (ref "U1") (pin "7") (pinfunction "CHRG_7") (pintype "unspecified"))
    )
    (net (code "42") (name "Net-(U1-PROG)") (class "Default")
      (node (ref "R5") (pin "1") (pinfunction "1_1") (pintype "input"))
      (node (ref "U1") (pin "2") (pinfunction "PROG_2") (pintype "unspecified"))
    )
    (net (code "43") (name "Net-(U3-LNA_IN)") (class "Default")
      (node (ref "C9") (pin "1") (pinfunction "1_1") (pintype "input"))
      (node (ref "R8") (pin "2") (pinfunction "2_2") (pintype "input"))
      (node (ref "U3") (pin "1") (pinfunction "LNA_IN_1") (pintype "unspecified"))
    )
    (net (code "44") (name "Net-(U3-XTAL_N)") (class "Default")
      (node (ref "C14") (pin "2") (pinfunction "2_2") (pintype "input"))
      (node (ref "U3") (pin "29") (pinfunction "XTAL_N_29") (pintype "unspecified"))
      (node (ref "X1") (pin "3") (pinfunction "3_3") (pintype "input"))
    )
    (net (code "45") (name "Net-(U3-XTAL_P)") (class "Default")
      (node (ref "L2") (pin "2") (pinfunction "2_2") (pintype "unspecified"))
      (node (ref "U3") (pin "30") (pinfunction "XTAL_P_30") (pintype "unspecified"))
    )
    (net (code "46") (name "Net-(U4-DIN)") (class "Default")
      (node (ref "R12") (pin "2") (pinfunction "2_2") (pintype "input"))
      (node (ref "U4") (pin "4") (pinfunction "DIN_4") (pintype "unspecified"))
    )
    (net (code "47") (name "Net-(U5-IO2)") (class "Default")
      (node (ref "R13") (pin "2") (pinfunction "2_2") (pintype "input"))
      (node (ref "U5") (pin "3") (pinfunction "IO2_3") (pintype "unspecified"))
    )
    (net (code "48") (name "Net-(U5-IO3)") (class "Default")
      (node (ref "R14") (pin "1") (pinfunction "1_1") (pintype "input"))
      (node (ref "U5") (pin "7") (pinfunction "IO3_7") (pintype "unspecified"))
    )
    (net (code "49") (name "Net-(U6-Bypass)") (class "Default")
      (node (ref "C28") (pin "2") (pinfunction "2_2") (pintype "input"))
      (node (ref "U6") (pin "2") (pinfunction "Bypass_2") (pintype "unspecified"))
    )
    (net (code "50") (name "Net-(U6-INN)") (class "Default")
      (node (ref "R20") (pin "1") (pinfunction "1_1") (pintype "input"))
      (node (ref "U6") (pin "4") (pinfunction "INN_4") (pintype "unspecified"))
    )
    (net (code "51") (name "Net-(U6-INP)") (class "Default")
      (node (ref "R19") (pin "1") (pinfunction "1_1") (pintype "input"))
      (node (ref "U6") (pin "3") (pinfunction "INP_3") (pintype "unspecified"))
    )
    (net (code "52") (name "Net-(U7-DACVREF)") (class "Default")
      (node (ref "C21") (pin "2") (pinfunction "2_2") (pintype "input"))
      (node (ref "U7") (pin "14") (pinfunction "DACVREF_14") (pintype "input"))
    )
    (net (code "53") (name "Net-(U7-MIC1N)") (class "Default")
      (node (ref "C25") (pin "2") (pinfunction "2_2") (pintype "input"))
      (node (ref "U7") (pin "17") (pinfunction "MIC1N_17") (pintype "input"))
    )
    (net (code "54") (name "Net-(U7-MIC1P{slash}DMIC_SDA)") (class "Default")
      (node (ref "C24") (pin "2") (pinfunction "2_2") (pintype "input"))
      (node (ref "U7") (pin "18") (pinfunction "MIC1P/DMIC_SDA_18") (pintype "input"))
    )
    (net (code "55") (name "Net-(U7-OUTN)") (class "Default")
      (node (ref "C32") (pin "2") (pinfunction "2_2") (pintype "input"))
      (node (ref "U7") (pin "13") (pinfunction "OUTN_13") (pintype "input"))
    )
    (net (code "56") (name "Net-(U7-OUTP)") (class "Default")
      (node (ref "C31") (pin "2") (pinfunction "2_2") (pintype "input"))
      (node (ref "U7") (pin "12") (pinfunction "OUTP_12") (pintype "input"))
    )
    (net (code "57") (name "Net-(U7-VMID)") (class "Default")
      (node (ref "C23") (pin "2") (pinfunction "2_2") (pintype "input"))
      (node (ref "U7") (pin "16") (pinfunction "VMID_16") (pintype "input"))
    )
    (net (code "58") (name "Net-(USB1-CC1)") (class "Default")
      (node (ref "R2") (pin "1") (pinfunction "1_1") (pintype "input"))
      (node (ref "USB1") (pin "4") (pinfunction "CC1_4") (pintype "unspecified"))
    )
    (net (code "59") (name "Net-(USB1-CC2)") (class "Default")
      (node (ref "R1") (pin "1") (pinfunction "1_1") (pintype "input"))
      (node (ref "USB1") (pin "10") (pinfunction "CC2_10") (pintype "unspecified"))
    )
    (net (code "60") (name "PA-GND") (class "Default")
      (node (ref "C19") (pin "1") (pinfunction "1_1") (pintype "input"))
    )
    (net (code "61") (name "PA_EN") (class "Default")
      (node (ref "R18") (pin "1") (pinfunction "1_1") (pintype "input"))
      (node (ref "U3") (pin "18") (pinfunction "VDD_SPI_18") (pintype "unspecified"))
      (node (ref "U6") (pin "1") (pinfunction "CTRL_1") (pintype "unspecified"))
    )
    (net (code "62") (name "PA_GND") (class "Default")
      (node (ref "C17") (pin "1") (pinfunction "1_1") (pintype "input"))
      (node (ref "C18") (pin "1") (pinfunction "1_1") (pintype "input"))
      (node (ref "C20") (pin "2") (pinfunction "2_2") (pintype "input"))
      (node (ref "C28") (pin "1") (pinfunction "1_1") (pintype "input"))
      (node (ref "R15") (pin "1") (pinfunction "1_1") (pintype "input"))
      (node (ref "R18") (pin "2") (pinfunction "2_2") (pintype "input"))
      (node (ref "U6") (pin "7") (pinfunction "GND_7") (pintype "unspecified"))
    )
    (net (code "63") (name "VSYS") (class "Default")
      (node (ref "C17") (pin "2") (pinfunction "2_2") (pintype "input"))
      (node (ref "C18") (pin "2") (pinfunction "2_2") (pintype "input"))
      (node (ref "C2") (pin "2") (pinfunction "2_2") (pintype "input"))
      (node (ref "SW1") (pin "3") (pinfunction "3_3") (pintype "unspecified"))
      (node (ref "U2") (pin "1") (pinfunction "VIN_1") (pintype "unspecified"))
      (node (ref "U2") (pin "3") (pinfunction "CE_3") (pintype "unspecified"))
      (node (ref "U4") (pin "2") (pinfunction "VDD_2") (pintype "unspecified"))
      (node (ref "U6") (pin "6") (pinfunction "VCC_6") (pintype "unspecified"))
    )
    (net (code "64") (name "unconnected-(ANT1-Pad2)") (class "Default")
      (node (ref "ANT1") (pin "2") (pinfunction "2_2") (pintype "unspecified+no_connect"))
    )
    (net (code "65") (name "unconnected-(BOOT1-Pad3)") (class "Default")
      (node (ref "BOOT1") (pin "3") (pinfunction "3_3") (pintype "unspecified+no_connect"))
    )
    (net (code "66") (name "unconnected-(BOOT1-Pad4)") (class "Default")
      (node (ref "BOOT1") (pin "4") (pinfunction "4_4") (pintype "unspecified+no_connect"))
    )
    (net (code "67") (name "unconnected-(CN1-Pad3)") (class "Default")
      (node (ref "CN1") (pin "3") (pinfunction "3_3") (pintype "unspecified+no_connect"))
    )
    (net (code "68") (name "unconnected-(CN1-Pad4)") (class "Default")
      (node (ref "CN1") (pin "4") (pinfunction "4_4") (pintype "unspecified+no_connect"))
    )
    (net (code "69") (name "unconnected-(CN2-Pad3)") (class "Default")
      (node (ref "CN2") (pin "3") (pinfunction "3_3") (pintype "unspecified+no_connect"))
    )
    (net (code "70") (name "unconnected-(CN2-Pad4)") (class "Default")
      (node (ref "CN2") (pin "4") (pinfunction "4_4") (pintype "unspecified+no_connect"))
    )
    (net (code "71") (name "unconnected-(OLED1-GND-Pad1)") (class "Default")
      (node (ref "OLED1") (pin "1") (pinfunction "GND_1") (pintype "input"))
    )
    (net (code "72") (name "unconnected-(OLED1-SCL-Pad3)") (class "Default")
      (node (ref "OLED1") (pin "3") (pinfunction "SCL_3") (pintype "input"))
    )
    (net (code "73") (name "unconnected-(OLED1-SDA-Pad4)") (class "Default")
      (node (ref "OLED1") (pin "4") (pinfunction "SDA_4") (pintype "input"))
    )
    (net (code "74") (name "unconnected-(OLED1-VCC-Pad2)") (class "Default")
      (node (ref "OLED1") (pin "2") (pinfunction "VCC_2") (pintype "input"))
    )
    (net (code "75") (name "unconnected-(SW1-Pad1)") (class "Default")
      (node (ref "SW1") (pin "1") (pinfunction "1_1") (pintype "unspecified+no_connect"))
    )
    (net (code "76") (name "unconnected-(SW1-Pad4)") (class "Default")
      (node (ref "SW1") (pin "4") (pinfunction "4_4") (pintype "unspecified+no_connect"))
    )
    (net (code "77") (name "unconnected-(SW1-Pad5)") (class "Default")
      (node (ref "SW1") (pin "5") (pinfunction "5_5") (pintype "unspecified+no_connect"))
    )
    (net (code "78") (name "unconnected-(U1-DONE-Pad6)") (class "Default")
      (node (ref "U1") (pin "6") (pinfunction "DONE_6") (pintype "unspecified+no_connect"))
    )
    (net (code "79") (name "unconnected-(U1-TEMP-Pad1)") (class "Default")
      (node (ref "U1") (pin "1") (pinfunction "TEMP_1") (pintype "unspecified+no_connect"))
    )
    (net (code "80") (name "unconnected-(U2-NC-Pad4)") (class "Default")
      (node (ref "U2") (pin "4") (pinfunction "NC_4") (pintype "unspecified+no_connect"))
    )
    (net (code "81") (name "unconnected-(U3-SPIHD-Pad19)") (class "Default")
      (node (ref "U3") (pin "19") (pinfunction "SPIHD_19") (pintype "unspecified+no_connect"))
    )
    (net (code "82") (name "unconnected-(U3-SPIWP-Pad20)") (class "Default")
      (node (ref "U3") (pin "20") (pinfunction "SPIWP_20") (pintype "unspecified+no_connect"))
    )
    (net (code "83") (name "unconnected-(U3-U0RXD-Pad27)") (class "Default")
      (node (ref "U3") (pin "27") (pinfunction "U0RXD_27") (pintype "unspecified+no_connect"))
    )
    (net (code "84") (name "unconnected-(U3-U0TXD-Pad28)") (class "Default")
      (node (ref "U3") (pin "28") (pinfunction "U0TXD_28") (pintype "unspecified+no_connect"))
    )
    (net (code "85") (name "unconnected-(U3-XTAL_32K_N-Pad5)") (class "Default")
      (node (ref "U3") (pin "5") (pinfunction "XTAL_32K_N_5") (pintype "unspecified+no_connect"))
    )
    (net (code "86") (name "unconnected-(U3-XTAL_32K_P-Pad4)") (class "Default")
      (node (ref "U3") (pin "4") (pinfunction "XTAL_32K_P_4") (pintype "unspecified+no_connect"))
    )
    (net (code "87") (name "unconnected-(U4-DOUT-Pad1)") (class "Default")
      (node (ref "U4") (pin "1") (pinfunction "DOUT_1") (pintype "unspecified+no_connect"))
    )
    (net (code "88") (name "unconnected-(USB1-SBU1-Pad9)") (class "Default")
      (node (ref "USB1") (pin "9") (pinfunction "SBU1_9") (pintype "unspecified+no_connect"))
    )
    (net (code "89") (name "unconnected-(USB1-SBU2-Pad3)") (class "Default")
      (node (ref "USB1") (pin "3") (pinfunction "SBU2_3") (pintype "unspecified+no_connect"))
    )
  )
)
